# DMB-4771-Relais.net
KiCad netlist of a schematic drawn in EAGLE
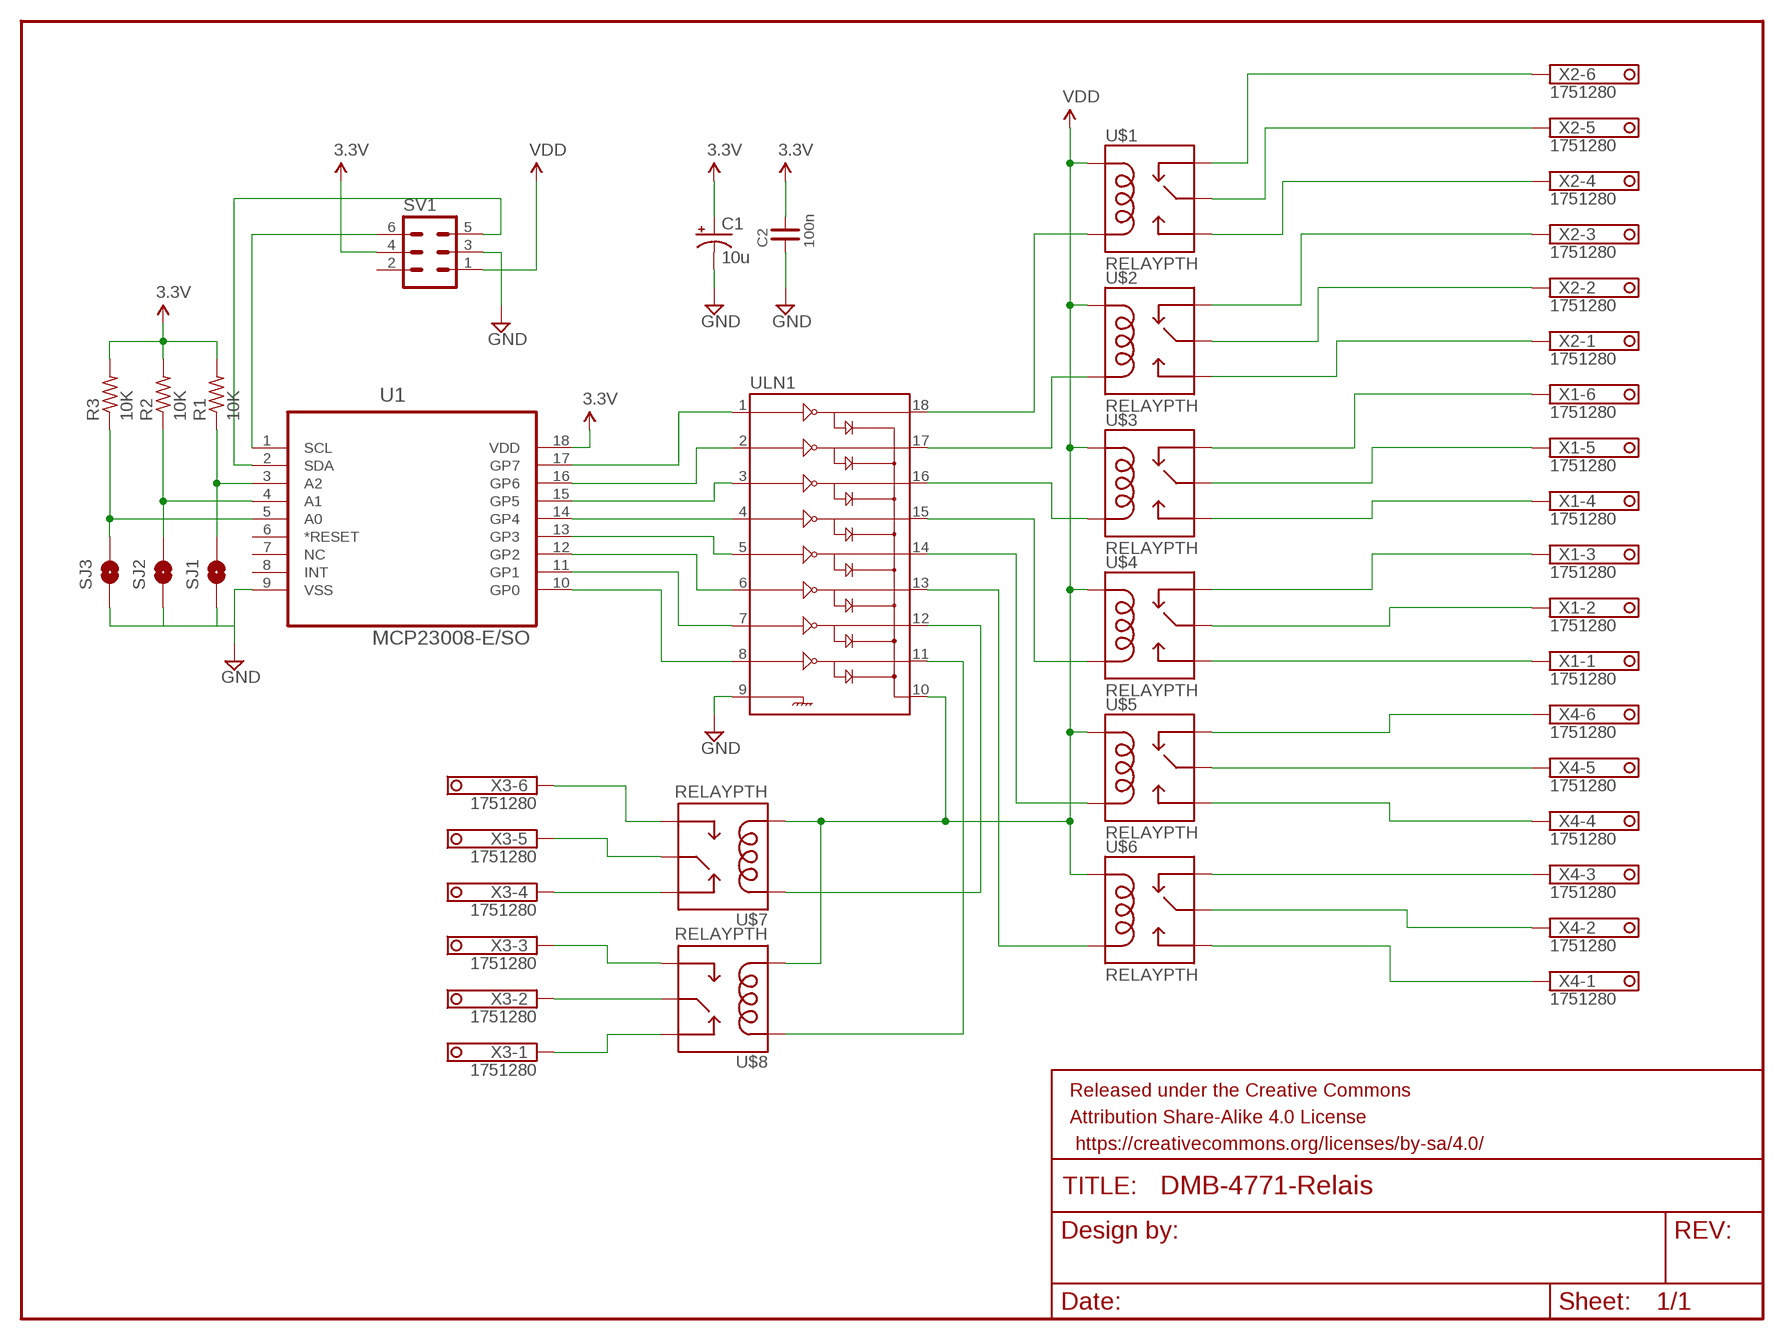
[diagram p0: schematic, sheet 1]

(export (version "E")
  (design (tool "Eeschema 10.0.6"))
  (components
    (comp (ref "C1")
      (value "10u")
      (footprint "eagle-import:EIA3216")
      (libsource (lib "eagle-import") (part "CAP_POL1206"))
    )
    (comp (ref "C2")
      (value "100n")
      (footprint "eagle-import:C0805")
      (libsource (lib "eagle-import") (part "C0805"))
    )
    (comp (ref "FRAME1")
      (value "FRAME-LETTER")
      (footprint "eagle-import:CREATIVE_COMMONS")
      (libsource (lib "eagle-import") (part "FRAME-LETTER"))
    )
    (comp (ref "R1")
      (value "10K")
      (footprint "eagle-import:R0805")
      (libsource (lib "eagle-import") (part "R-US_R0805"))
    )
    (comp (ref "R2")
      (value "10K")
      (footprint "eagle-import:R0805")
      (libsource (lib "eagle-import") (part "R-US_R0805"))
    )
    (comp (ref "R3")
      (value "10K")
      (footprint "eagle-import:R0805")
      (libsource (lib "eagle-import") (part "R-US_R0805"))
    )
    (comp (ref "SJ1")
      (value "JUMPER-PAD-2-NOYES_SILK")
      (footprint "eagle-import:PAD-JUMPER-2-NO_YES_SILK")
      (libsource (lib "eagle-import") (part "JUMPER-PAD-2-NOYES_SILK"))
    )
    (comp (ref "SJ2")
      (value "JUMPER-PAD-2-NOYES_SILK")
      (footprint "eagle-import:PAD-JUMPER-2-NO_YES_SILK")
      (libsource (lib "eagle-import") (part "JUMPER-PAD-2-NOYES_SILK"))
    )
    (comp (ref "SJ3")
      (value "JUMPER-PAD-2-NOYES_SILK")
      (footprint "eagle-import:PAD-JUMPER-2-NO_YES_SILK")
      (libsource (lib "eagle-import") (part "JUMPER-PAD-2-NOYES_SILK"))
    )
    (comp (ref "SV1")
      (value "ML6")
      (footprint "eagle-import:ML6")
      (libsource (lib "eagle-import") (part "ML6"))
    )
    (comp (ref "U$1")
      (value "RELAYPTH")
      (footprint "eagle-import:RELAY-G5Q")
      (libsource (lib "eagle-import") (part "RELAYPTH"))
    )
    (comp (ref "U$2")
      (value "RELAYPTH")
      (footprint "eagle-import:RELAY-G5Q")
      (libsource (lib "eagle-import") (part "RELAYPTH"))
    )
    (comp (ref "U$3")
      (value "RELAYPTH")
      (footprint "eagle-import:RELAY-G5Q")
      (libsource (lib "eagle-import") (part "RELAYPTH"))
    )
    (comp (ref "U$4")
      (value "RELAYPTH")
      (footprint "eagle-import:RELAY-G5Q")
      (libsource (lib "eagle-import") (part "RELAYPTH"))
    )
    (comp (ref "U$5")
      (value "RELAYPTH")
      (footprint "eagle-import:RELAY-G5Q")
      (libsource (lib "eagle-import") (part "RELAYPTH"))
    )
    (comp (ref "U$6")
      (value "RELAYPTH")
      (footprint "eagle-import:RELAY-G5Q")
      (libsource (lib "eagle-import") (part "RELAYPTH"))
    )
    (comp (ref "U$7")
      (value "RELAYPTH")
      (footprint "eagle-import:RELAY-G5Q")
      (libsource (lib "eagle-import") (part "RELAYPTH"))
    )
    (comp (ref "U$8")
      (value "RELAYPTH")
      (footprint "eagle-import:RELAY-G5Q")
      (libsource (lib "eagle-import") (part "RELAYPTH"))
    )
    (comp (ref "U1")
      (value "MCP23008-E/SO")
      (footprint "eagle-import:SOIC127P1030X265-18N")
      (libsource (lib "eagle-import") (part "MCP23008-E/SO"))
    )
    (comp (ref "ULN1")
      (value "ULN2803SOIC")
      (footprint "eagle-import:SO018")
      (libsource (lib "eagle-import") (part "ULN2803SOIC"))
    )
    (comp (ref "X1")
      (value "1751280")
      (footprint "eagle-import:1751280")
      (libsource (lib "eagle-import") (part "1751280"))
    )
    (comp (ref "X2")
      (value "1751280")
      (footprint "eagle-import:1751280")
      (libsource (lib "eagle-import") (part "1751280"))
    )
    (comp (ref "X3")
      (value "1751280")
      (footprint "eagle-import:1751280")
      (libsource (lib "eagle-import") (part "1751280"))
    )
    (comp (ref "X4")
      (value "1751280")
      (footprint "eagle-import:1751280")
      (libsource (lib "eagle-import") (part "1751280"))
    )
  )
  (nets
    (net (code "1") (name "3.3V") (class "Default")
      (node (ref "C1") (pin "A") (pinfunction "+_A") (pintype "passive"))
      (node (ref "C2") (pin "2") (pinfunction "2_2") (pintype "passive"))
      (node (ref "R1") (pin "2") (pinfunction "2_2") (pintype "passive"))
      (node (ref "R2") (pin "2") (pinfunction "2_2") (pintype "passive"))
      (node (ref "R3") (pin "2") (pinfunction "2_2") (pintype "passive"))
      (node (ref "SV1") (pin "4") (pinfunction "4_4") (pintype "passive"))
      (node (ref "U1") (pin "18") (pinfunction "VDD_18") (pintype "power_in"))
    )
    (net (code "2") (name "GND") (class "Default")
      (node (ref "C1") (pin "C") (pinfunction "-_C") (pintype "passive"))
      (node (ref "C2") (pin "1") (pinfunction "1_1") (pintype "passive"))
      (node (ref "SJ1") (pin "1") (pinfunction "1_1") (pintype "passive"))
      (node (ref "SJ2") (pin "1") (pinfunction "1_1") (pintype "passive"))
      (node (ref "SJ3") (pin "1") (pinfunction "1_1") (pintype "passive"))
      (node (ref "SV1") (pin "3") (pinfunction "3_3") (pintype "passive"))
      (node (ref "U1") (pin "9") (pinfunction "VSS_9") (pintype "passive"))
      (node (ref "ULN1") (pin "9") (pinfunction "9_9") (pintype "bidirectional"))
    )
    (net (code "3") (name "Net-(U$1-COIL2)") (class "Default")
      (node (ref "U$1") (pin "1") (pinfunction "COIL2_1") (pintype "bidirectional"))
      (node (ref "ULN1") (pin "18") (pinfunction "18_18") (pintype "bidirectional"))
    )
    (net (code "4") (name "Net-(U$1-MAIN)") (class "Default")
      (node (ref "U$1") (pin "2") (pinfunction "MAIN_2") (pintype "bidirectional"))
      (node (ref "X2") (pin "5") (pinfunction "K_5") (pintype "passive"))
    )
    (net (code "5") (name "Net-(U$1-NC)") (class "Default")
      (node (ref "U$1") (pin "4") (pinfunction "NC_4") (pintype "bidirectional"))
      (node (ref "X2") (pin "6") (pinfunction "K_6") (pintype "passive"))
    )
    (net (code "6") (name "Net-(U$1-NO)") (class "Default")
      (node (ref "U$1") (pin "3") (pinfunction "NO_3") (pintype "bidirectional"))
      (node (ref "X2") (pin "4") (pinfunction "K_4") (pintype "passive"))
    )
    (net (code "7") (name "Net-(U$2-COIL2)") (class "Default")
      (node (ref "U$2") (pin "1") (pinfunction "COIL2_1") (pintype "bidirectional"))
      (node (ref "ULN1") (pin "17") (pinfunction "17_17") (pintype "bidirectional"))
    )
    (net (code "8") (name "Net-(U$2-MAIN)") (class "Default")
      (node (ref "U$2") (pin "2") (pinfunction "MAIN_2") (pintype "bidirectional"))
      (node (ref "X2") (pin "2") (pinfunction "K_2") (pintype "passive"))
    )
    (net (code "9") (name "Net-(U$2-NC)") (class "Default")
      (node (ref "U$2") (pin "4") (pinfunction "NC_4") (pintype "bidirectional"))
      (node (ref "X2") (pin "3") (pinfunction "K_3") (pintype "passive"))
    )
    (net (code "10") (name "Net-(U$2-NO)") (class "Default")
      (node (ref "U$2") (pin "3") (pinfunction "NO_3") (pintype "bidirectional"))
      (node (ref "X2") (pin "1") (pinfunction "K_1") (pintype "passive"))
    )
    (net (code "11") (name "Net-(U$3-COIL2)") (class "Default")
      (node (ref "U$3") (pin "1") (pinfunction "COIL2_1") (pintype "bidirectional"))
      (node (ref "ULN1") (pin "16") (pinfunction "16_16") (pintype "bidirectional"))
    )
    (net (code "12") (name "Net-(U$3-MAIN)") (class "Default")
      (node (ref "U$3") (pin "2") (pinfunction "MAIN_2") (pintype "bidirectional"))
      (node (ref "X1") (pin "5") (pinfunction "K_5") (pintype "passive"))
    )
    (net (code "13") (name "Net-(U$3-NC)") (class "Default")
      (node (ref "U$3") (pin "4") (pinfunction "NC_4") (pintype "bidirectional"))
      (node (ref "X1") (pin "6") (pinfunction "K_6") (pintype "passive"))
    )
    (net (code "14") (name "Net-(U$3-NO)") (class "Default")
      (node (ref "U$3") (pin "3") (pinfunction "NO_3") (pintype "bidirectional"))
      (node (ref "X1") (pin "4") (pinfunction "K_4") (pintype "passive"))
    )
    (net (code "15") (name "Net-(U$4-COIL2)") (class "Default")
      (node (ref "U$4") (pin "1") (pinfunction "COIL2_1") (pintype "bidirectional"))
      (node (ref "ULN1") (pin "15") (pinfunction "15_15") (pintype "bidirectional"))
    )
    (net (code "16") (name "Net-(U$4-MAIN)") (class "Default")
      (node (ref "U$4") (pin "2") (pinfunction "MAIN_2") (pintype "bidirectional"))
      (node (ref "X1") (pin "2") (pinfunction "K_2") (pintype "passive"))
    )
    (net (code "17") (name "Net-(U$4-NC)") (class "Default")
      (node (ref "U$4") (pin "4") (pinfunction "NC_4") (pintype "bidirectional"))
      (node (ref "X1") (pin "3") (pinfunction "K_3") (pintype "passive"))
    )
    (net (code "18") (name "Net-(U$4-NO)") (class "Default")
      (node (ref "U$4") (pin "3") (pinfunction "NO_3") (pintype "bidirectional"))
      (node (ref "X1") (pin "1") (pinfunction "K_1") (pintype "passive"))
    )
    (net (code "19") (name "Net-(U$5-COIL2)") (class "Default")
      (node (ref "U$5") (pin "1") (pinfunction "COIL2_1") (pintype "bidirectional"))
      (node (ref "ULN1") (pin "14") (pinfunction "14_14") (pintype "bidirectional"))
    )
    (net (code "20") (name "Net-(U$5-MAIN)") (class "Default")
      (node (ref "U$5") (pin "2") (pinfunction "MAIN_2") (pintype "bidirectional"))
      (node (ref "X4") (pin "5") (pinfunction "K_5") (pintype "passive"))
    )
    (net (code "21") (name "Net-(U$5-NC)") (class "Default")
      (node (ref "U$5") (pin "4") (pinfunction "NC_4") (pintype "bidirectional"))
      (node (ref "X4") (pin "6") (pinfunction "K_6") (pintype "passive"))
    )
    (net (code "22") (name "Net-(U$5-NO)") (class "Default")
      (node (ref "U$5") (pin "3") (pinfunction "NO_3") (pintype "bidirectional"))
      (node (ref "X4") (pin "4") (pinfunction "K_4") (pintype "passive"))
    )
    (net (code "23") (name "Net-(U$6-COIL2)") (class "Default")
      (node (ref "U$6") (pin "1") (pinfunction "COIL2_1") (pintype "bidirectional"))
      (node (ref "ULN1") (pin "13") (pinfunction "13_13") (pintype "bidirectional"))
    )
    (net (code "24") (name "Net-(U$6-MAIN)") (class "Default")
      (node (ref "U$6") (pin "2") (pinfunction "MAIN_2") (pintype "bidirectional"))
      (node (ref "X4") (pin "2") (pinfunction "K_2") (pintype "passive"))
    )
    (net (code "25") (name "Net-(U$6-NC)") (class "Default")
      (node (ref "U$6") (pin "4") (pinfunction "NC_4") (pintype "bidirectional"))
      (node (ref "X4") (pin "3") (pinfunction "K_3") (pintype "passive"))
    )
    (net (code "26") (name "Net-(U$6-NO)") (class "Default")
      (node (ref "U$6") (pin "3") (pinfunction "NO_3") (pintype "bidirectional"))
      (node (ref "X4") (pin "1") (pinfunction "K_1") (pintype "passive"))
    )
    (net (code "27") (name "Net-(U$7-COIL1)") (class "Default")
      (node (ref "U$7") (pin "5") (pinfunction "COIL1_5") (pintype "bidirectional"))
      (node (ref "ULN1") (pin "12") (pinfunction "12_12") (pintype "bidirectional"))
    )
    (net (code "28") (name "Net-(U$7-MAIN)") (class "Default")
      (node (ref "U$7") (pin "2") (pinfunction "MAIN_2") (pintype "bidirectional"))
      (node (ref "X3") (pin "5") (pinfunction "K_5") (pintype "passive"))
    )
    (net (code "29") (name "Net-(U$7-NC)") (class "Default")
      (node (ref "U$7") (pin "4") (pinfunction "NC_4") (pintype "bidirectional"))
      (node (ref "X3") (pin "4") (pinfunction "K_4") (pintype "passive"))
    )
    (net (code "30") (name "Net-(U$7-NO)") (class "Default")
      (node (ref "U$7") (pin "3") (pinfunction "NO_3") (pintype "bidirectional"))
      (node (ref "X3") (pin "6") (pinfunction "K_6") (pintype "passive"))
    )
    (net (code "31") (name "Net-(U$8-COIL1)") (class "Default")
      (node (ref "U$8") (pin "5") (pinfunction "COIL1_5") (pintype "bidirectional"))
      (node (ref "ULN1") (pin "11") (pinfunction "11_11") (pintype "bidirectional"))
    )
    (net (code "32") (name "Net-(U$8-MAIN)") (class "Default")
      (node (ref "U$8") (pin "2") (pinfunction "MAIN_2") (pintype "bidirectional"))
      (node (ref "X3") (pin "2") (pinfunction "K_2") (pintype "passive"))
    )
    (net (code "33") (name "Net-(U$8-NC)") (class "Default")
      (node (ref "U$8") (pin "4") (pinfunction "NC_4") (pintype "bidirectional"))
      (node (ref "X3") (pin "1") (pinfunction "K_1") (pintype "passive"))
    )
    (net (code "34") (name "Net-(U$8-NO)") (class "Default")
      (node (ref "U$8") (pin "3") (pinfunction "NO_3") (pintype "bidirectional"))
      (node (ref "X3") (pin "3") (pinfunction "K_3") (pintype "passive"))
    )
    (net (code "35") (name "Net-(U1-A0)") (class "Default")
      (node (ref "R3") (pin "1") (pinfunction "1_1") (pintype "passive"))
      (node (ref "SJ3") (pin "2") (pinfunction "2_2") (pintype "passive"))
      (node (ref "U1") (pin "5") (pinfunction "A0_5") (pintype "input"))
    )
    (net (code "36") (name "Net-(U1-A1)") (class "Default")
      (node (ref "R2") (pin "1") (pinfunction "1_1") (pintype "passive"))
      (node (ref "SJ2") (pin "2") (pinfunction "2_2") (pintype "passive"))
      (node (ref "U1") (pin "4") (pinfunction "A1_4") (pintype "input"))
    )
    (net (code "37") (name "Net-(U1-A2)") (class "Default")
      (node (ref "R1") (pin "1") (pinfunction "1_1") (pintype "passive"))
      (node (ref "SJ1") (pin "2") (pinfunction "2_2") (pintype "passive"))
      (node (ref "U1") (pin "3") (pinfunction "A2_3") (pintype "passive"))
    )
    (net (code "38") (name "Net-(U1-GP0)") (class "Default")
      (node (ref "U1") (pin "10") (pinfunction "GP0_10") (pintype "passive"))
      (node (ref "ULN1") (pin "8") (pinfunction "8_8") (pintype "bidirectional"))
    )
    (net (code "39") (name "Net-(U1-GP1)") (class "Default")
      (node (ref "U1") (pin "11") (pinfunction "GP1_11") (pintype "passive"))
      (node (ref "ULN1") (pin "7") (pinfunction "7_7") (pintype "bidirectional"))
    )
    (net (code "40") (name "Net-(U1-GP2)") (class "Default")
      (node (ref "U1") (pin "12") (pinfunction "GP2_12") (pintype "passive"))
      (node (ref "ULN1") (pin "6") (pinfunction "6_6") (pintype "bidirectional"))
    )
    (net (code "41") (name "Net-(U1-GP3)") (class "Default")
      (node (ref "U1") (pin "13") (pinfunction "GP3_13") (pintype "passive"))
      (node (ref "ULN1") (pin "5") (pinfunction "5_5") (pintype "bidirectional"))
    )
    (net (code "42") (name "Net-(U1-GP4)") (class "Default")
      (node (ref "U1") (pin "14") (pinfunction "GP4_14") (pintype "passive"))
      (node (ref "ULN1") (pin "4") (pinfunction "4_4") (pintype "bidirectional"))
    )
    (net (code "43") (name "Net-(U1-GP5)") (class "Default")
      (node (ref "U1") (pin "15") (pinfunction "GP5_15") (pintype "passive"))
      (node (ref "ULN1") (pin "3") (pinfunction "3_3") (pintype "bidirectional"))
    )
    (net (code "44") (name "Net-(U1-GP6)") (class "Default")
      (node (ref "U1") (pin "16") (pinfunction "GP6_16") (pintype "passive"))
      (node (ref "ULN1") (pin "2") (pinfunction "2_2") (pintype "bidirectional"))
    )
    (net (code "45") (name "Net-(U1-GP7)") (class "Default")
      (node (ref "U1") (pin "17") (pinfunction "GP7_17") (pintype "passive"))
      (node (ref "ULN1") (pin "1") (pinfunction "1_1") (pintype "bidirectional"))
    )
    (net (code "46") (name "Net-(U1-SCL)") (class "Default")
      (node (ref "SV1") (pin "6") (pinfunction "6_6") (pintype "passive"))
      (node (ref "U1") (pin "1") (pinfunction "SCL_1") (pintype "input"))
    )
    (net (code "47") (name "Net-(U1-SDA)") (class "Default")
      (node (ref "SV1") (pin "5") (pinfunction "5_5") (pintype "passive"))
      (node (ref "U1") (pin "2") (pinfunction "SDA_2") (pintype "passive"))
    )
    (net (code "48") (name "VDD") (class "Default")
      (node (ref "SV1") (pin "1") (pinfunction "1_1") (pintype "passive"))
      (node (ref "U$1") (pin "5") (pinfunction "COIL1_5") (pintype "bidirectional"))
      (node (ref "U$2") (pin "5") (pinfunction "COIL1_5") (pintype "bidirectional"))
      (node (ref "U$3") (pin "5") (pinfunction "COIL1_5") (pintype "bidirectional"))
      (node (ref "U$4") (pin "5") (pinfunction "COIL1_5") (pintype "bidirectional"))
      (node (ref "U$5") (pin "5") (pinfunction "COIL1_5") (pintype "bidirectional"))
      (node (ref "U$6") (pin "5") (pinfunction "COIL1_5") (pintype "bidirectional"))
      (node (ref "U$7") (pin "1") (pinfunction "COIL2_1") (pintype "bidirectional"))
      (node (ref "U$8") (pin "1") (pinfunction "COIL2_1") (pintype "bidirectional"))
      (node (ref "ULN1") (pin "10") (pinfunction "10_10") (pintype "bidirectional"))
    )
    (net (code "49") (name "unconnected-(SV1-Pad2)") (class "Default")
      (node (ref "SV1") (pin "2") (pinfunction "2_2") (pintype "passive"))
    )
    (net (code "50") (name "unconnected-(U1-*RESET-Pad6)") (class "Default")
      (node (ref "U1") (pin "6") (pinfunction "*RESET_6") (pintype "input"))
    )
    (net (code "51") (name "unconnected-(U1-INT-Pad8)") (class "Default")
      (node (ref "U1") (pin "8") (pinfunction "INT_8") (pintype "output"))
    )
    (net (code "52") (name "unconnected-(U1-NC-Pad7)") (class "Default")
      (node (ref "U1") (pin "7") (pinfunction "NC_7") (pintype "input"))
    )
  )
)
